# Key.net
KiCad netlist of a schematic drawn in Altium Designer
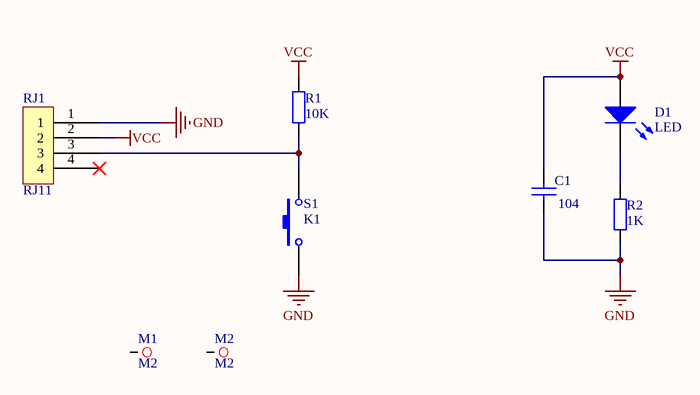
[diagram p0: Key.SchDoc]

(export (version "E")
  (design (tool "Eeschema 10.0.6"))
  (components
    (comp (ref "C1")
      (value "104")
      (footprint "0603_C")
      (description "Capacitor")
      (fields (field (name "Comment") "Cap") (field (name "PUBLISHER") "Altium Limited"))
      (libsource (lib "Miscellaneous Devices") (part "Cap"))
    )
    (comp (ref "D1")
      (value "LED")
      (footprint "0805")
      (description "Typical RED GaAs LED")
      (fields (field (name "PUBLISHER") "Altium Limited"))
      (libsource (lib "Miscellaneous Devices") (part "LED1"))
    )
    (comp (ref "M1") (value "M2") (footprint "M2") (libsource (lib "QQW-1.SCHLIB") (part "M3")))
    (comp (ref "M2") (value "M2") (footprint "M2") (libsource (lib "QQW-1.SCHLIB") (part "M3")))
    (comp (ref "R1")
      (value "10K")
      (footprint "0603_R")
      (description "Resistor")
      (fields (field (name "Comment") "Res2") (field (name "PUBLISHER") "Altium Limited"))
      (libsource (lib "Miscellaneous Devices") (part "Res2"))
    )
    (comp (ref "R2")
      (value "1K")
      (footprint "0603_R")
      (description "Resistor")
      (fields (field (name "Comment") "Res2") (field (name "PUBLISHER") "Altium Limited"))
      (libsource (lib "") (part "Res2_1"))
    )
    (comp (ref "RJ1") (value "RJ11") (footprint "RJ11") (libsource (lib "少儿智能车") (part "RJ11")))
    (comp (ref "S1")
      (value "K1")
      (footprint "Key-12*12*7.3")
      (description "Switch")
      (fields (field (name "PUBLISHER") "Altium Limited"))
      (libsource (lib "Miscellaneous Devices") (part "SW-PB"))
    )
  )
  (nets
    (net (code "1") (name "GND") (class "Default")
      (node (ref "C1") (pin "1") (pinfunction "1_1") (pintype "passive"))
      (node (ref "R2") (pin "1") (pinfunction "1_1") (pintype "passive"))
      (node (ref "RJ1") (pin "1") (pinfunction "1_1") (pintype "passive"))
      (node (ref "S1") (pin "1") (pinfunction "1_1") (pintype "passive"))
    )
    (net (code "2") (name "Net-(D1-K)") (class "Default")
      (node (ref "D1") (pin "2") (pinfunction "K_2") (pintype "passive"))
      (node (ref "R2") (pin "2") (pinfunction "2_2") (pintype "passive"))
    )
    (net (code "3") (name "Net-(R1-Pad2)") (class "Default")
      (node (ref "R1") (pin "2") (pinfunction "2_2") (pintype "passive"))
      (node (ref "RJ1") (pin "3") (pinfunction "3_3") (pintype "passive"))
      (node (ref "S1") (pin "2") (pinfunction "2_2") (pintype "passive"))
    )
    (net (code "4") (name "VCC") (class "Default")
      (node (ref "C1") (pin "2") (pinfunction "2_2") (pintype "passive"))
      (node (ref "D1") (pin "1") (pinfunction "A_1") (pintype "passive"))
      (node (ref "R1") (pin "1") (pinfunction "1_1") (pintype "passive"))
      (node (ref "RJ1") (pin "2") (pinfunction "2_2") (pintype "passive"))
    )
    (net (code "5") (name "unconnected-(M1-Pad0)") (class "Default")
      (node (ref "M1") (pin "0") (pinfunction "0_0") (pintype "passive"))
    )
    (net (code "6") (name "unconnected-(M2-Pad0)") (class "Default")
      (node (ref "M2") (pin "0") (pinfunction "0_0") (pintype "passive"))
    )
    (net (code "7") (name "unconnected-(RJ1-Pad4)") (class "Default")
      (node (ref "RJ1") (pin "4") (pinfunction "4_4") (pintype "passive+no_connect"))
    )
  )
)
